# 14-RegenSolenoid.net
KiCad netlist of a schematic drawn in Altium Designer
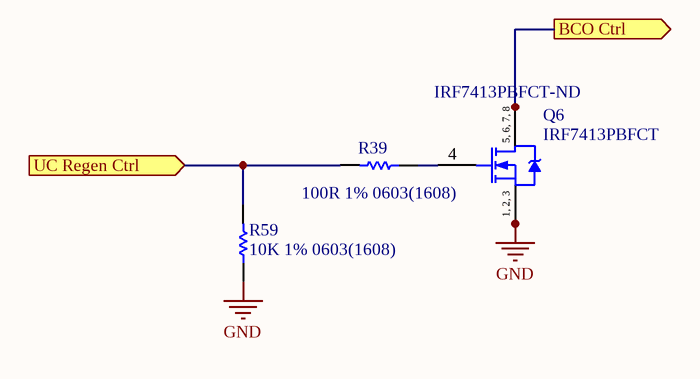
[diagram p0: 14-RegenSolenoid.SchDoc]

(export (version "E")
  (design (tool "Eeschema 10.0.6"))
  (components
    (comp (ref "Q6")
      (value "IRF7413PBFCT")
      (footprint "INTR-SO-8_V")
      (description "HEXFET (R) Power MOSFET, 30 V, -55 to 150 degC, 8-Pin SO, RoHS, Tube")
      (fields
        (field (name "MANUFACTURER") "International Rectifier")
        (field (name "SUPPLIER PART NUMBER 1") "IRF7413PBFCT-ND")
      )
      (libsource (lib "Altium Content Vault") (part "NEMOS-SSSGDDDD-8-B"))
    )
    (comp (ref "R39")
      (value "100R 1% 0603(1608)")
      (footprint "RESC0603(1608)_N")
      (description "100R 0.1W 1% 0603 (1608 Metric)  SMD")
      (fields (field (name "TOLERANCE") "1 %") (field (name "POWER") "0.1 W"))
      (libsource (lib "Altium Content Vault") (part "RES"))
    )
    (comp (ref "R59")
      (value "10K 1% 0603(1608)")
      (footprint "RESC0603(1608)_N")
      (description "10K 0.1W 1% 0603 (1608 Metric)  SMD")
      (fields (field (name "POWER") "0.1 W") (field (name "TOLERANCE") "1 %"))
      (libsource (lib "Altium Content Vault") (part "RES"))
    )
  )
  (nets
    (net (code "1") (name "/BCO Ctrl") (class "Default")
      (node (ref "Q6") (pin "5") (pinfunction "D_5") (pintype "passive"))
      (node (ref "Q6") (pin "6") (pinfunction "D_6") (pintype "passive"))
      (node (ref "Q6") (pin "7") (pinfunction "D_7") (pintype "passive"))
      (node (ref "Q6") (pin "8") (pinfunction "D_8") (pintype "passive"))
    )
    (net (code "2") (name "/UC Regen Ctrl") (class "Default")
      (node (ref "R39") (pin "2") (pinfunction "2_2") (pintype "passive"))
      (node (ref "R59") (pin "2") (pinfunction "2_2") (pintype "passive"))
    )
    (net (code "3") (name "GND") (class "Default")
      (node (ref "Q6") (pin "1") (pinfunction "S_1") (pintype "passive"))
      (node (ref "Q6") (pin "2") (pinfunction "S_2") (pintype "passive"))
      (node (ref "Q6") (pin "3") (pinfunction "S_3") (pintype "passive"))
      (node (ref "R59") (pin "1") (pinfunction "1_1") (pintype "passive"))
    )
    (net (code "4") (name "Net-(Q6-G)") (class "Default")
      (node (ref "Q6") (pin "4") (pinfunction "G_4") (pintype "passive"))
      (node (ref "R39") (pin "1") (pinfunction "1_1") (pintype "passive"))
    )
  )
)
